# LED_SOP.net
KiCad netlist of a schematic drawn in Altium Designer
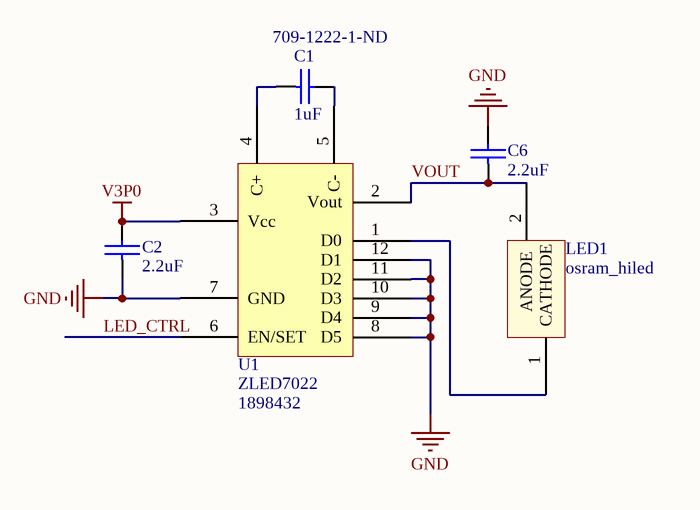
[diagram p0: LED_SOP.SchDoc]

(export (version "E")
  (design (tool "Eeschema 10.0.6"))
  (components
    (comp (ref "C1")
      (value "1uF")
      (footprint "0402l")
      (description "Capacitor")
      (fields
        (field (name "SUPPLIER PART NUMBER 1") "709-1222-1-ND")
        (field (name "MANUFACTURER") "Johanson Dielectrics Inc")
        (field (name "MANUFACTURER PART NUMBER") "100R07X105KV4T")
      )
      (libsource (lib "nRF24LE1F16Q24") (part "Cap"))
    )
    (comp (ref "C2")
      (value "2.2uF")
      (footprint "0402l")
      (description "Capacitor")
      (fields (field (name "Comment") "NP0 50V"))
      (libsource (lib "nRF24LE1F16Q24") (part "Cap"))
    )
    (comp (ref "C6")
      (value "2.2uF")
      (footprint "0402l")
      (description "Capacitor")
      (fields (field (name "Comment") "NP0 50V"))
      (libsource (lib "nRF24LE1F16Q24") (part "Cap"))
    )
    (comp (ref "LED1")
      (value "osram_hiled")
      (footprint "osram_led_cn5m")
      (libsource (lib "custom") (part "osram_hiled"))
    )
    (comp (ref "U1")
      (value "ZLED7022")
      (footprint "12utqfn")
      (description "ZLED 7022")
      (fields
        (field (name "SUPPLIER PART NUMBER 1") "1898432")
        (field (name "MANUFACTURER") "ZMDI")
        (field (name "MANUFACTURER PART NUMBER") "ZLED7022-ZI1R")
      )
      (libsource (lib "custom") (part "ZLED7022"))
    )
  )
  (nets
    (net (code "1") (name "/LED_CTRL") (class "Default")
      (node (ref "U1") (pin "6") (pinfunction "EN/SET_6") (pintype "passive"))
    )
    (net (code "2") (name "/VOUT") (class "Default")
      (node (ref "C6") (pin "1") (pintype "passive"))
      (node (ref "LED1") (pin "2") (pinfunction "ANODE_2") (pintype "passive"))
      (node (ref "U1") (pin "2") (pinfunction "Vout_2") (pintype "passive"))
    )
    (net (code "3") (name "GND") (class "Default")
      (node (ref "C2") (pin "1") (pintype "passive"))
      (node (ref "C6") (pin "2") (pintype "passive"))
      (node (ref "U1") (pin "10") (pinfunction "D3_10") (pintype "passive"))
      (node (ref "U1") (pin "11") (pinfunction "D2_11") (pintype "passive"))
      (node (ref "U1") (pin "12") (pinfunction "D1_12") (pintype "passive"))
      (node (ref "U1") (pin "7") (pinfunction "GND_7") (pintype "passive"))
      (node (ref "U1") (pin "8") (pinfunction "D5_8") (pintype "passive"))
      (node (ref "U1") (pin "9") (pinfunction "D4_9") (pintype "passive"))
    )
    (net (code "4") (name "Net-(LED1-CATHODE)") (class "Default")
      (node (ref "LED1") (pin "1") (pinfunction "CATHODE_1") (pintype "passive"))
      (node (ref "U1") (pin "1") (pinfunction "D0_1") (pintype "passive"))
    )
    (net (code "5") (name "Net-(U1-C+)") (class "Default")
      (node (ref "C1") (pin "1") (pintype "passive"))
      (node (ref "U1") (pin "4") (pinfunction "C+_4") (pintype "passive"))
    )
    (net (code "6") (name "Net-(U1-C-)") (class "Default")
      (node (ref "C1") (pin "2") (pintype "passive"))
      (node (ref "U1") (pin "5") (pinfunction "C-_5") (pintype "passive"))
    )
    (net (code "7") (name "V3P0") (class "Default")
      (node (ref "C2") (pin "2") (pintype "passive"))
      (node (ref "U1") (pin "3") (pinfunction "Vcc_3") (pintype "passive"))
    )
  )
)
